# board2.net
KiCad netlist of a schematic drawn in EAGLE
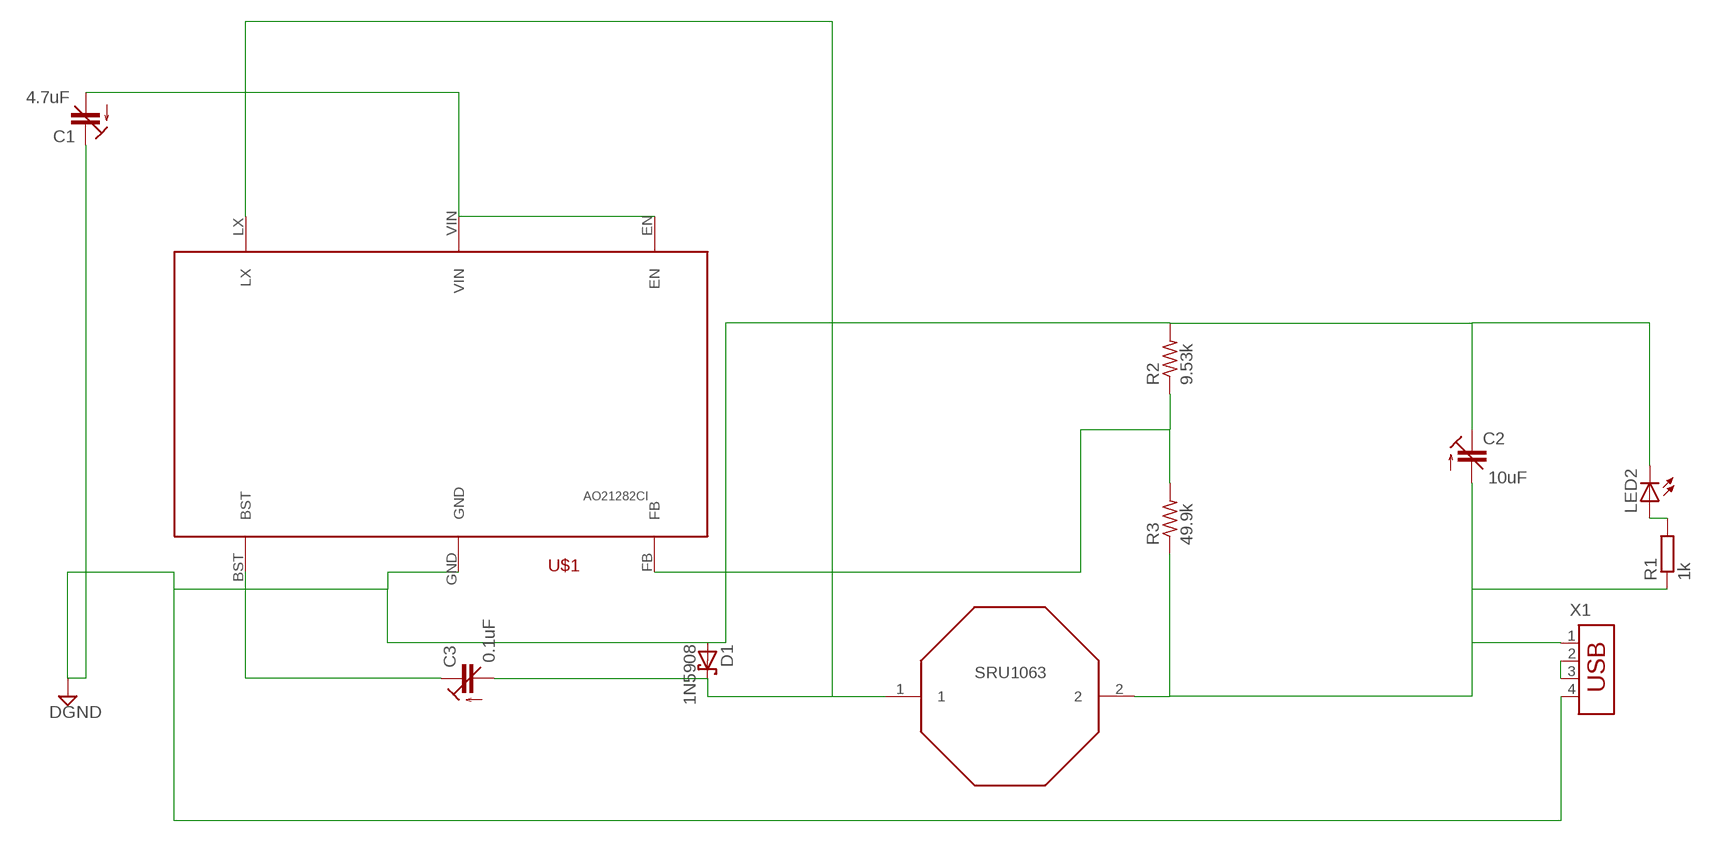
[diagram p0: schematic, sheet 1]

(export (version "E")
  (design (tool "Eeschema 10.0.6"))
  (components
    (comp (ref "C1")
      (value "4.7uF")
      (footprint "eagle-import:3008")
      (libsource (lib "eagle-import") (part "C-TRIMM3008"))
    )
    (comp (ref "C2")
      (value "10uF")
      (footprint "eagle-import:3008")
      (libsource (lib "eagle-import") (part "C-TRIMM3008"))
    )
    (comp (ref "C3")
      (value "0.1uF")
      (footprint "eagle-import:3008")
      (libsource (lib "eagle-import") (part "C-TRIMM3008"))
    )
    (comp (ref "D1")
      (value "1N5908")
      (footprint "eagle-import:C4111-15")
      (libsource (lib "eagle-import") (part "1N5908"))
    )
    (comp (ref "LED2")
      (value "LEDSML0603")
      (footprint "eagle-import:SML0603")
      (libsource (lib "eagle-import") (part "LEDSML0603"))
    )
    (comp (ref "R1")
      (value "1k")
      (footprint "eagle-import:R1206")
      (libsource (lib "eagle-import") (part "R-EU_R1206"))
    )
    (comp (ref "R2")
      (value "9.53k")
      (footprint "eagle-import:M1206")
      (libsource (lib "eagle-import") (part "R-US_M1206"))
    )
    (comp (ref "R3")
      (value "49.9k")
      (footprint "eagle-import:M1206")
      (libsource (lib "eagle-import") (part "R-US_M1206"))
    )
    (comp (ref "U$1")
      (value "AO21282CI")
      (footprint "eagle-import:AO21282CI")
      (libsource (lib "eagle-import") (part "AO21282CI"))
    )
    (comp (ref "U$2")
      (value "SRU1063")
      (footprint "eagle-import:SRU1063")
      (libsource (lib "eagle-import") (part "SRU1063"))
    )
    (comp (ref "X1")
      (value "USB-787616")
      (footprint "eagle-import:USB")
      (libsource (lib "eagle-import") (part "USB-787616"))
    )
  )
  (nets
    (net (code "1") (name "DGND") (class "Default")
      (node (ref "C1") (pin "+") (pinfunction "E_+") (pintype "passive"))
      (node (ref "C2") (pin "+") (pinfunction "E_+") (pintype "passive"))
      (node (ref "D1") (pin "A") (pinfunction "A_A") (pintype "passive"))
      (node (ref "LED2") (pin "C") (pinfunction "C_C") (pintype "passive"))
      (node (ref "R2") (pin "2") (pinfunction "2_2") (pintype "passive"))
      (node (ref "U$1") (pin "GND") (pinfunction "GND_GND") (pintype "bidirectional"))
      (node (ref "X1") (pin "4") (pinfunction "4_4") (pintype "passive"))
    )
    (net (code "2") (name "Net-(C1-A)") (class "Default")
      (node (ref "C1") (pin "-") (pinfunction "A_-") (pintype "passive"))
      (node (ref "U$1") (pin "EN") (pinfunction "EN_EN") (pintype "bidirectional"))
      (node (ref "U$1") (pin "VIN") (pinfunction "VIN_VIN") (pintype "bidirectional"))
    )
    (net (code "3") (name "Net-(C2-A)") (class "Default")
      (node (ref "C2") (pin "-") (pinfunction "A_-") (pintype "passive"))
      (node (ref "R1") (pin "1") (pinfunction "1_1") (pintype "passive"))
      (node (ref "R3") (pin "1") (pinfunction "1_1") (pintype "passive"))
      (node (ref "U$2") (pin "2") (pinfunction "2_2") (pintype "bidirectional"))
      (node (ref "X1") (pin "1") (pinfunction "1_1") (pintype "passive"))
    )
    (net (code "4") (name "Net-(C3-A)") (class "Default")
      (node (ref "C3") (pin "-") (pinfunction "A_-") (pintype "passive"))
      (node (ref "D1") (pin "C") (pinfunction "C_C") (pintype "passive"))
      (node (ref "U$1") (pin "LX") (pinfunction "LX_LX") (pintype "bidirectional"))
      (node (ref "U$2") (pin "1") (pinfunction "1_1") (pintype "bidirectional"))
    )
    (net (code "5") (name "Net-(C3-E)") (class "Default")
      (node (ref "C3") (pin "+") (pinfunction "E_+") (pintype "passive"))
      (node (ref "U$1") (pin "BST") (pinfunction "BST_BST") (pintype "bidirectional"))
    )
    (net (code "6") (name "Net-(LED2-PadA)") (class "Default")
      (node (ref "LED2") (pin "A") (pinfunction "A_A") (pintype "passive"))
      (node (ref "R1") (pin "2") (pinfunction "2_2") (pintype "passive"))
    )
    (net (code "7") (name "Net-(R2-Pad1)") (class "Default")
      (node (ref "R2") (pin "1") (pinfunction "1_1") (pintype "passive"))
      (node (ref "R3") (pin "2") (pinfunction "2_2") (pintype "passive"))
      (node (ref "U$1") (pin "FB") (pinfunction "FB_FB") (pintype "bidirectional"))
    )
    (net (code "8") (name "Net-(X1-Pad2)") (class "Default")
      (node (ref "X1") (pin "2") (pinfunction "2_2") (pintype "passive"))
      (node (ref "X1") (pin "3") (pinfunction "3_3") (pintype "passive"))
    )
  )
)
